# Sheet1.net
KiCad netlist of a schematic drawn in Altium Designer
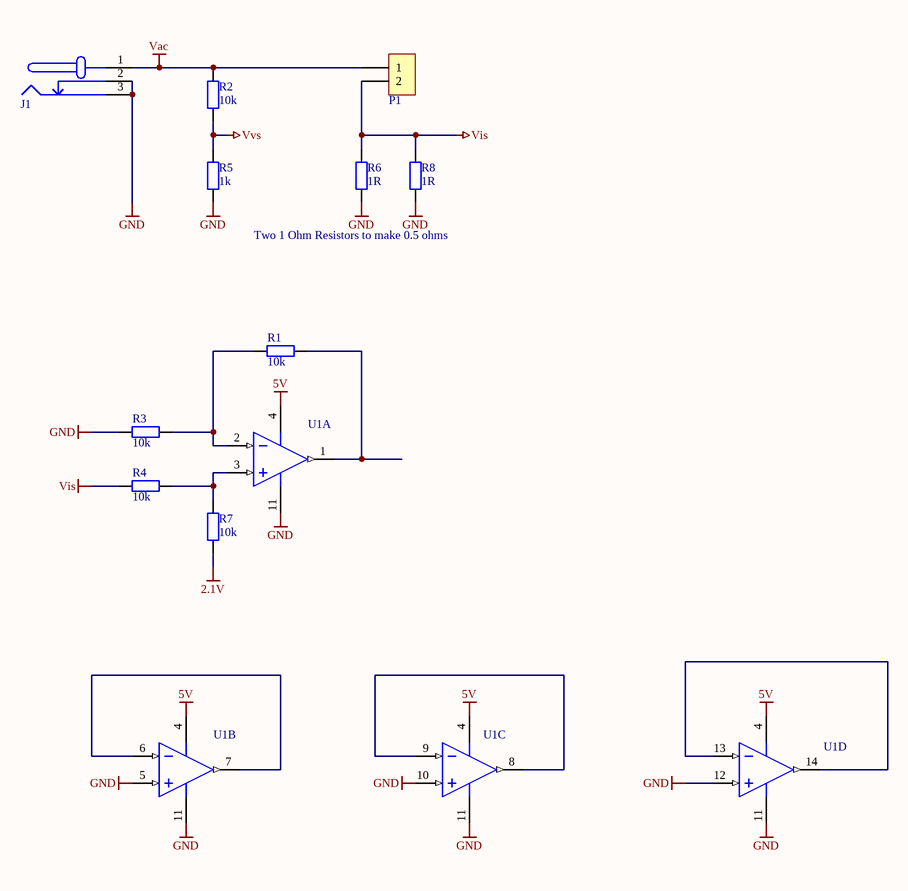
[diagram p0: Sheet1.SchDoc]

(export (version "E")
  (design (tool "Eeschema 10.0.6"))
  (components
    (comp (ref "J1")
      (value "DC barrel jack")
      (footprint "AC-Socket")
      (description "DC barrel jack connection to AC source")
      (libsource (lib "EE209_Library") (part "AC_Input"))
    )
    (comp (ref "P1")
      (value "Dual Banana Plugs")
      (footprint "Dual Banana Plug")
      (description "Dual banana plugs connection to the AC load")
      (fields (field (name "PUBLISHER") "Altium Limited"))
      (libsource (lib "EE209_Library") (part "AC_Output"))
    )
    (comp (ref "R1")
      (value "10k")
      (footprint "AXIAL-0.4")
      (description "Through hole resistor")
      (fields (field (name "PUBLISHER") "Altium Limited"))
      (libsource (lib "") (part "Res_TH_0AX4_1"))
    )
    (comp (ref "R2")
      (value "10k")
      (footprint "AXIAL-0.4")
      (description "Through hole resistor")
      (fields (field (name "PUBLISHER") "Altium Limited"))
      (libsource (lib "EE209_Library") (part "Res_TH_0AX4"))
    )
    (comp (ref "R3")
      (value "10k")
      (footprint "AXIAL-0.4")
      (description "Through hole resistor")
      (fields (field (name "PUBLISHER") "Altium Limited"))
      (libsource (lib "") (part "Res_TH_0AX4_1"))
    )
    (comp (ref "R4")
      (value "10k")
      (footprint "AXIAL-0.4")
      (description "Through hole resistor")
      (fields (field (name "PUBLISHER") "Altium Limited"))
      (libsource (lib "") (part "Res_TH_0AX4_1"))
    )
    (comp (ref "R5")
      (value "1k")
      (footprint "AXIAL-0.4")
      (description "Through hole resistor")
      (fields (field (name "PUBLISHER") "Altium Limited"))
      (libsource (lib "EE209_Library") (part "Res_TH_0AX4"))
    )
    (comp (ref "R6")
      (value "1R")
      (footprint "AXIAL-0.4")
      (description "Through hole resistor")
      (fields (field (name "PUBLISHER") "Altium Limited"))
      (libsource (lib "EE209_Library") (part "Res_TH_0AX4"))
    )
    (comp (ref "R7")
      (value "10k")
      (footprint "AXIAL-0.4")
      (description "Through hole resistor")
      (fields (field (name "PUBLISHER") "Altium Limited"))
      (libsource (lib "EE209_Library") (part "Res_TH_0AX4"))
    )
    (comp (ref "R8")
      (value "1R")
      (footprint "AXIAL-0.4")
      (description "Through hole resistor")
      (fields (field (name "PUBLISHER") "Altium Limited"))
      (libsource (lib "EE209_Library") (part "Res_TH_0AX4"))
    )
    (comp (ref "U1")
      (value "LM324")
      (footprint "DIP-14")
      (description "IC OPAMP GP 14DIP")
      (fields
        (field (name "MANUFACTURER") "ON Semiconductor")
        (field (name "MANUFACTURER PART NUMBER") "LM324N")
      )
      (libsource (lib "EE209_Library") (part "LM324N_TH_DIP16"))
    )
  )
  (nets
    (net (code "1") (name "2.1V") (class "Default")
      (node (ref "R7") (pin "1") (pinfunction "1_1") (pintype "passive"))
    )
    (net (code "2") (name "5V") (class "Default")
      (node (ref "U1") (pin "4") (pinfunction "VDD_4") (pintype "power_in"))
    )
    (net (code "3") (name "GND") (class "Default")
      (node (ref "J1") (pin "2") (pinfunction "GND_ALT_2") (pintype "power_in"))
      (node (ref "J1") (pin "3") (pinfunction "GND_3") (pintype "power_in"))
      (node (ref "R3") (pin "1") (pinfunction "1_1") (pintype "passive"))
      (node (ref "R5") (pin "1") (pinfunction "1_1") (pintype "passive"))
      (node (ref "R6") (pin "1") (pinfunction "1_1") (pintype "passive"))
      (node (ref "R8") (pin "1") (pinfunction "1_1") (pintype "passive"))
      (node (ref "U1") (pin "10") (pinfunction "VINC+_10") (pintype "input"))
      (node (ref "U1") (pin "11") (pinfunction "VSS_11") (pintype "power_in"))
      (node (ref "U1") (pin "12") (pinfunction "VIND+_12") (pintype "input"))
      (node (ref "U1") (pin "5") (pinfunction "VINB+_5") (pintype "input"))
    )
    (net (code "4") (name "Net-(U1A-VINA+)") (class "Default")
      (node (ref "R4") (pin "2") (pinfunction "2_2") (pintype "passive"))
      (node (ref "R7") (pin "2") (pinfunction "2_2") (pintype "passive"))
      (node (ref "U1") (pin "3") (pinfunction "VINA+_3") (pintype "input"))
    )
    (net (code "5") (name "Net-(U1A-VINA-)") (class "Default")
      (node (ref "R1") (pin "1") (pinfunction "1_1") (pintype "passive"))
      (node (ref "R3") (pin "2") (pinfunction "2_2") (pintype "passive"))
      (node (ref "U1") (pin "2") (pinfunction "VINA-_2") (pintype "input"))
    )
    (net (code "6") (name "Net-(U1A-VOUTA)") (class "Default")
      (node (ref "R1") (pin "2") (pinfunction "2_2") (pintype "passive"))
      (node (ref "U1") (pin "1") (pinfunction "VOUTA_1") (pintype "output"))
    )
    (net (code "7") (name "Net-(U1B-VINB-)") (class "Default")
      (node (ref "U1") (pin "6") (pinfunction "VINB-_6") (pintype "input"))
      (node (ref "U1") (pin "7") (pinfunction "VOUTB_7") (pintype "output"))
    )
    (net (code "8") (name "Net-(U1C-VINC-)") (class "Default")
      (node (ref "U1") (pin "8") (pinfunction "VOUTC_8") (pintype "output"))
      (node (ref "U1") (pin "9") (pinfunction "VINC-_9") (pintype "input"))
    )
    (net (code "9") (name "Net-(U1D-VIND-)") (class "Default")
      (node (ref "U1") (pin "13") (pinfunction "VIND-_13") (pintype "input"))
      (node (ref "U1") (pin "14") (pinfunction "VOUTD_14") (pintype "output"))
    )
    (net (code "10") (name "Vac") (class "Default")
      (node (ref "J1") (pin "1") (pinfunction "VCC_1") (pintype "power_in"))
      (node (ref "P1") (pin "1") (pinfunction "1_1") (pintype "passive"))
      (node (ref "R2") (pin "2") (pinfunction "2_2") (pintype "passive"))
    )
    (net (code "11") (name "Vis") (class "Default")
      (node (ref "P1") (pin "2") (pinfunction "2_2") (pintype "passive"))
      (node (ref "R4") (pin "1") (pinfunction "1_1") (pintype "passive"))
      (node (ref "R6") (pin "2") (pinfunction "2_2") (pintype "passive"))
      (node (ref "R8") (pin "2") (pinfunction "2_2") (pintype "passive"))
    )
    (net (code "12") (name "Vvs") (class "Default")
      (node (ref "R2") (pin "1") (pinfunction "1_1") (pintype "passive"))
      (node (ref "R5") (pin "2") (pinfunction "2_2") (pintype "passive"))
    )
  )
)
